# 06-AD9546_TimestampInputs.net
KiCad netlist of a schematic drawn in Altium Designer
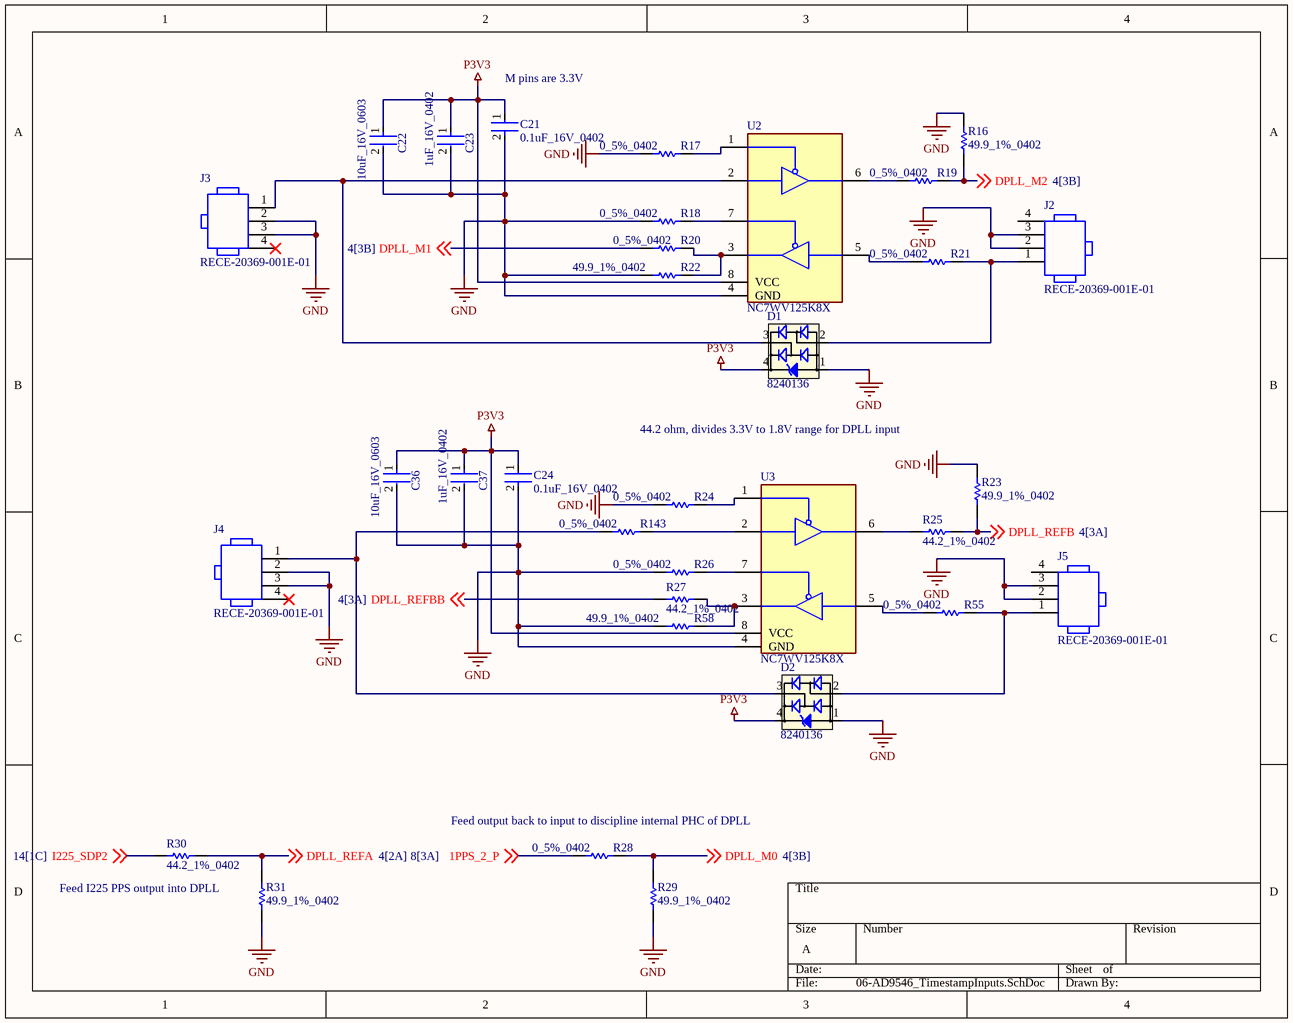
[diagram p0: 06-AD9546_TimestampInputs.SchDoc]

(export (version "E")
  (design (tool "Eeschema 10.0.6"))
  (components
    (comp (ref "C21")
      (value "GRM155R71C104KA88D")
      (footprint "FP-GRM15-MFG")
      (description "CAP CER 0.1UF 16V X7R 0402")
      (fields
        (field (name "TOLERANCE") "10%")
        (field (name "OCTOPART") "https://octopart.com/grm155r71c104ka88d-murata-196880")
        (field (name "DIGIKEY DESCRIPTION") "0.1uF_16V_0402")
      )
      (libsource (lib "Altium Content Vault") (part "236180d848d6139a670b325ea6854c9"))
    )
    (comp (ref "C22")
      (value "10uF_16V_0603")
      (footprint "FP-C1608-MFG")
      (description "CAP CER 10UF 16V X5R 0603")
      (fields
        (field (name "OCTOPART") "https://octopart.com/c1608x5r1c106m080ab-tdk-26013480")
        (field (name "MANUFACTURER") "TDK Corporation")
      )
      (libsource (lib "Altium Content Vault") (part "11868f565c42a9108669ba33697ecf6"))
    )
    (comp (ref "C23")
      (value "1uF_16V_0402")
      (footprint "FP-0402-L_1_0_0_05-W_0_5-IPC_C")
      (description "None")
      (fields (field (name "TOLERANCE") "20%") (field (name "VOLTAGE") "16V"))
      (libsource (lib "Altium Content Vault") (part "b4654b650e69147ec39a6b967a45e02"))
    )
    (comp (ref "C24")
      (value "GRM155R71C104KA88D")
      (footprint "FP-GRM15-MFG")
      (description "CAP CER 0.1UF 16V X7R 0402")
      (fields
        (field (name "TOLERANCE") "10%")
        (field (name "OCTOPART") "https://octopart.com/grm155r71c104ka88d-murata-196880")
        (field (name "DIGIKEY DESCRIPTION") "0.1uF_16V_0402")
      )
      (libsource (lib "Altium Content Vault") (part "236180d848d6139a670b325ea6854c9"))
    )
    (comp (ref "C36")
      (value "10uF_16V_0603")
      (footprint "FP-C1608-MFG")
      (description "CAP CER 10UF 16V X5R 0603")
      (fields
        (field (name "OCTOPART") "https://octopart.com/c1608x5r1c106m080ab-tdk-26013480")
        (field (name "MANUFACTURER") "TDK Corporation")
      )
      (libsource (lib "Altium Content Vault") (part "11868f565c42a9108669ba33697ecf6"))
    )
    (comp (ref "C37")
      (value "1uF_16V_0402")
      (footprint "FP-0402-L_1_0_0_05-W_0_5-IPC_C")
      (description "None")
      (fields (field (name "TOLERANCE") "20%") (field (name "VOLTAGE") "16V"))
      (libsource (lib "Altium Content Vault") (part "b4654b650e69147ec39a6b967a45e02"))
    )
    (comp (ref "D1")
      (value "8240136")
      (footprint "SOT143-4L")
      (description "TVS Diode WE-TVS-HS, VRWM=3.3V")
      (fields (field (name "MANUFACTURER") "Wuerth Elektronik"))
      (libsource (lib "Altium Content Vault") (part "WE-TVS-HS-4"))
    )
    (comp (ref "D2")
      (value "8240136")
      (footprint "SOT143-4L")
      (description "TVS Diode WE-TVS-HS, VRWM=3.3V")
      (fields (field (name "MANUFACTURER") "Wuerth Elektronik"))
      (libsource (lib "Altium Content Vault") (part "WE-TVS-HS-4"))
    )
    (comp (ref "J2")
      (value "RECE-20369-001E-01")
      (footprint "TG-RECE-20369-001E-4_V")
      (description "RF Connector, Onboard Receptacle, IPEX MHFIII")
      (fields (field (name "MANUFACTURER") "Taoglas"))
      (libsource (lib "Altium Content Vault") (part "TG-RECE-20369-001E-01-4"))
    )
    (comp (ref "J3")
      (value "RECE-20369-001E-01")
      (footprint "TG-RECE-20369-001E-4_V")
      (description "RF Connector, Onboard Receptacle, IPEX MHFIII")
      (fields (field (name "MANUFACTURER") "Taoglas"))
      (libsource (lib "Altium Content Vault") (part "TG-RECE-20369-001E-01-4"))
    )
    (comp (ref "J4")
      (value "RECE-20369-001E-01")
      (footprint "TG-RECE-20369-001E-4_V")
      (description "RF Connector, Onboard Receptacle, IPEX MHFIII")
      (fields (field (name "MANUFACTURER") "Taoglas"))
      (libsource (lib "Altium Content Vault") (part "TG-RECE-20369-001E-01-4"))
    )
    (comp (ref "J5")
      (value "RECE-20369-001E-01")
      (footprint "TG-RECE-20369-001E-4_V")
      (description "RF Connector, Onboard Receptacle, IPEX MHFIII")
      (fields (field (name "MANUFACTURER") "Taoglas"))
      (libsource (lib "Altium Content Vault") (part "TG-RECE-20369-001E-01-4"))
    )
    (comp (ref "R16")
      (value "49.9_1%_0402")
      (footprint "RESC1005X40X25NL05T05")
      (fields (field (name "MANUFACTURER") "Panasonic") (field (name "PART NUMBER") "ERJ-2RKF49R9X"))
      (libsource (lib "Altium Content Vault") (part "RES"))
    )
    (comp (ref "R17")
      (value "0_5%_0402")
      (footprint "RESC1005X40X25LL10T10")
      (fields (field (name "MANUFACTURER") "KOA Speer") (field (name "PART NUMBER") "RK73Z1ETTP"))
      (libsource (lib "Altium Content Vault") (part "RES"))
    )
    (comp (ref "R18")
      (value "0_5%_0402")
      (footprint "RESC1005X40X25LL10T10")
      (fields (field (name "MANUFACTURER") "KOA Speer") (field (name "PART NUMBER") "RK73Z1ETTP"))
      (libsource (lib "Altium Content Vault") (part "RES"))
    )
    (comp (ref "R19")
      (value "0_5%_0402")
      (footprint "RESC1005X40X25LL10T10")
      (fields (field (name "MANUFACTURER") "KOA Speer") (field (name "PART NUMBER") "RK73Z1ETTP"))
      (libsource (lib "Altium Content Vault") (part "RES"))
    )
    (comp (ref "R20")
      (value "0_5%_0402")
      (footprint "RESC1005X40X25LL10T10")
      (fields (field (name "MANUFACTURER") "KOA Speer") (field (name "PART NUMBER") "RK73Z1ETTP"))
      (libsource (lib "Altium Content Vault") (part "RES"))
    )
    (comp (ref "R21")
      (value "0_5%_0402")
      (footprint "RESC1005X40X25LL10T10")
      (fields (field (name "MANUFACTURER") "KOA Speer") (field (name "PART NUMBER") "RK73Z1ETTP"))
      (libsource (lib "Altium Content Vault") (part "RES"))
    )
    (comp (ref "R22")
      (value "49.9_1%_0402")
      (footprint "RESC1005X40X25NL05T05")
      (fields (field (name "MANUFACTURER") "Panasonic") (field (name "PART NUMBER") "ERJ-2RKF49R9X"))
      (libsource (lib "Altium Content Vault") (part "RES"))
    )
    (comp (ref "R23")
      (value "49.9_1%_0402")
      (footprint "RESC1005X40X25NL05T05")
      (fields (field (name "MANUFACTURER") "Panasonic") (field (name "PART NUMBER") "ERJ-2RKF49R9X"))
      (libsource (lib "Altium Content Vault") (part "RES"))
    )
    (comp (ref "R24")
      (value "0_5%_0402")
      (footprint "RESC1005X40X25LL10T10")
      (fields (field (name "MANUFACTURER") "KOA Speer") (field (name "PART NUMBER") "RK73Z1ETTP"))
      (libsource (lib "Altium Content Vault") (part "RES"))
    )
    (comp (ref "R25")
      (value "44.2_1%_0402")
      (footprint "RESC1005X40X25LL05T05")
      (fields (field (name "MANUFACTURER") "Vishay Dale") (field (name "PART NUMBER") "CRCW040244R2FKED"))
      (libsource (lib "Altium Content Vault") (part "RES"))
    )
    (comp (ref "R26")
      (value "0_5%_0402")
      (footprint "RESC1005X40X25LL10T10")
      (fields (field (name "MANUFACTURER") "KOA Speer") (field (name "PART NUMBER") "RK73Z1ETTP"))
      (libsource (lib "Altium Content Vault") (part "RES"))
    )
    (comp (ref "R27")
      (value "44.2_1%_0402")
      (footprint "RESC1005X40X25LL05T05")
      (fields (field (name "MANUFACTURER") "Vishay Dale") (field (name "PART NUMBER") "CRCW040244R2FKED"))
      (libsource (lib "Altium Content Vault") (part "RES"))
    )
    (comp (ref "R28")
      (value "0_5%_0402")
      (footprint "RESC1005X40X25LL10T10")
      (fields (field (name "MANUFACTURER") "KOA Speer") (field (name "PART NUMBER") "RK73Z1ETTP"))
      (libsource (lib "Altium Content Vault") (part "RES"))
    )
    (comp (ref "R29")
      (value "49.9_1%_0402")
      (footprint "RESC1005X40X25NL05T05")
      (fields (field (name "MANUFACTURER") "Panasonic") (field (name "PART NUMBER") "ERJ-2RKF49R9X"))
      (libsource (lib "Altium Content Vault") (part "RES"))
    )
    (comp (ref "R30")
      (value "44.2_1%_0402")
      (footprint "RESC1005X40X25LL05T05")
      (fields (field (name "MANUFACTURER") "Vishay Dale") (field (name "PART NUMBER") "CRCW040244R2FKED"))
      (libsource (lib "Altium Content Vault") (part "RES"))
    )
    (comp (ref "R31")
      (value "49.9_1%_0402")
      (footprint "RESC1005X40X25NL05T05")
      (fields (field (name "MANUFACTURER") "Panasonic") (field (name "PART NUMBER") "ERJ-2RKF49R9X"))
      (libsource (lib "Altium Content Vault") (part "RES"))
    )
    (comp (ref "R55")
      (value "0_5%_0402")
      (footprint "RESC1005X40X25LL10T10")
      (fields (field (name "MANUFACTURER") "KOA Speer") (field (name "PART NUMBER") "RK73Z1ETTP"))
      (libsource (lib "Altium Content Vault") (part "RES"))
    )
    (comp (ref "R58")
      (value "49.9_1%_0402")
      (footprint "RESC1005X40X25NL05T05")
      (fields (field (name "MANUFACTURER") "Panasonic") (field (name "PART NUMBER") "ERJ-2RKF49R9X"))
      (libsource (lib "Altium Content Vault") (part "RES"))
    )
    (comp (ref "R143")
      (value "0_5%_0402")
      (footprint "RESC1005X40X25LL10T10")
      (fields (field (name "MANUFACTURER") "KOA Speer") (field (name "PART NUMBER") "RK73Z1ETTP"))
      (libsource (lib "Altium Content Vault") (part "RES"))
    )
    (comp (ref "U2")
      (value "NC7WV125K8X")
      (footprint "NC7WV125")
      (description "Integrated Circuit")
      (fields (field (name "MOUSER PART NUMBER") "512-NC7WV125K8X"))
      (libsource (lib "SamacSys") (part "NC7WV125K8X"))
    )
    (comp (ref "U3")
      (value "NC7WV125K8X")
      (footprint "NC7WV125")
      (description "Integrated Circuit")
      (fields (field (name "MOUSER PART NUMBER") "512-NC7WV125K8X"))
      (libsource (lib "SamacSys") (part "NC7WV125K8X"))
    )
  )
  (nets
    (net (code "1") (name "1PPS_2_P") (class "Default")
      (node (ref "R28") (pin "1") (pinfunction "1_1") (pintype "passive"))
    )
    (net (code "2") (name "DPLL_M0") (class "Default")
      (node (ref "R28") (pin "2") (pinfunction "2_2") (pintype "passive"))
      (node (ref "R29") (pin "2") (pinfunction "2_2") (pintype "passive"))
    )
    (net (code "3") (name "DPLL_M1") (class "Default")
      (node (ref "R20") (pin "1") (pinfunction "1_1") (pintype "passive"))
    )
    (net (code "4") (name "DPLL_M2") (class "Default")
      (node (ref "R16") (pin "1") (pinfunction "1_1") (pintype "passive"))
      (node (ref "R19") (pin "2") (pinfunction "2_2") (pintype "passive"))
    )
    (net (code "5") (name "DPLL_REFA") (class "Default")
      (node (ref "R30") (pin "2") (pinfunction "2_2") (pintype "passive"))
      (node (ref "R31") (pin "2") (pinfunction "2_2") (pintype "passive"))
    )
    (net (code "6") (name "DPLL_REFB") (class "Default")
      (node (ref "R23") (pin "1") (pinfunction "1_1") (pintype "passive"))
      (node (ref "R25") (pin "2") (pinfunction "2_2") (pintype "passive"))
    )
    (net (code "7") (name "DPLL_REFBB") (class "Default")
      (node (ref "R27") (pin "1") (pinfunction "1_1") (pintype "passive"))
    )
    (net (code "8") (name "GND") (class "Default")
      (node (ref "C21") (pin "2") (pinfunction "2_2") (pintype "passive"))
      (node (ref "C22") (pin "2") (pinfunction "2_2") (pintype "passive"))
      (node (ref "C23") (pin "2") (pinfunction "2_2") (pintype "passive"))
      (node (ref "C24") (pin "2") (pinfunction "2_2") (pintype "passive"))
      (node (ref "C36") (pin "2") (pinfunction "2_2") (pintype "passive"))
      (node (ref "C37") (pin "2") (pinfunction "2_2") (pintype "passive"))
      (node (ref "D1") (pin "1") (pinfunction "GND_1") (pintype "passive"))
      (node (ref "D2") (pin "1") (pinfunction "GND_1") (pintype "passive"))
      (node (ref "J2") (pin "2") (pinfunction "2_2") (pintype "passive"))
      (node (ref "J2") (pin "3") (pinfunction "3_3") (pintype "passive"))
      (node (ref "J3") (pin "2") (pinfunction "2_2") (pintype "passive"))
      (node (ref "J3") (pin "3") (pinfunction "3_3") (pintype "passive"))
      (node (ref "J4") (pin "2") (pinfunction "2_2") (pintype "passive"))
      (node (ref "J4") (pin "3") (pinfunction "3_3") (pintype "passive"))
      (node (ref "J5") (pin "2") (pinfunction "2_2") (pintype "passive"))
      (node (ref "J5") (pin "3") (pinfunction "3_3") (pintype "passive"))
      (node (ref "R16") (pin "2") (pinfunction "2_2") (pintype "passive"))
      (node (ref "R17") (pin "1") (pinfunction "1_1") (pintype "passive"))
      (node (ref "R18") (pin "1") (pinfunction "1_1") (pintype "passive"))
      (node (ref "R22") (pin "2") (pinfunction "2_2") (pintype "passive"))
      (node (ref "R23") (pin "2") (pinfunction "2_2") (pintype "passive"))
      (node (ref "R24") (pin "1") (pinfunction "1_1") (pintype "passive"))
      (node (ref "R26") (pin "1") (pinfunction "1_1") (pintype "passive"))
      (node (ref "R29") (pin "1") (pinfunction "1_1") (pintype "passive"))
      (node (ref "R31") (pin "1") (pinfunction "1_1") (pintype "passive"))
      (node (ref "R58") (pin "2") (pinfunction "2_2") (pintype "passive"))
      (node (ref "U2") (pin "4") (pinfunction "GND_4") (pintype "passive"))
      (node (ref "U3") (pin "4") (pinfunction "GND_4") (pintype "passive"))
    )
    (net (code "9") (name "I225_SDP2") (class "Default")
      (node (ref "R30") (pin "1") (pinfunction "1_1") (pintype "passive"))
    )
    (net (code "10") (name "Net-(D1-I{slash}O1)") (class "Default")
      (node (ref "D1") (pin "2") (pinfunction "I/O1_2") (pintype "passive"))
      (node (ref "J2") (pin "1") (pinfunction "1_1") (pintype "passive"))
      (node (ref "R21") (pin "2") (pinfunction "2_2") (pintype "passive"))
    )
    (net (code "11") (name "Net-(D1-I{slash}O2)") (class "Default")
      (node (ref "D1") (pin "3") (pinfunction "I/O2_3") (pintype "passive"))
      (node (ref "J3") (pin "1") (pinfunction "1_1") (pintype "passive"))
      (node (ref "U2") (pin "2") (pintype "passive"))
    )
    (net (code "12") (name "Net-(D2-I{slash}O1)") (class "Default")
      (node (ref "D2") (pin "2") (pinfunction "I/O1_2") (pintype "passive"))
      (node (ref "J5") (pin "1") (pinfunction "1_1") (pintype "passive"))
      (node (ref "R55") (pin "2") (pinfunction "2_2") (pintype "passive"))
    )
    (net (code "13") (name "Net-(D2-I{slash}O2)") (class "Default")
      (node (ref "D2") (pin "3") (pinfunction "I/O2_3") (pintype "passive"))
      (node (ref "J4") (pin "1") (pinfunction "1_1") (pintype "passive"))
      (node (ref "R143") (pin "1") (pinfunction "1_1") (pintype "passive"))
    )
    (net (code "14") (name "Net-(R17-Pad2)") (class "Default")
      (node (ref "R17") (pin "2") (pinfunction "2_2") (pintype "passive"))
      (node (ref "U2") (pin "1") (pintype "passive"))
    )
    (net (code "15") (name "Net-(R18-Pad2)") (class "Default")
      (node (ref "R18") (pin "2") (pinfunction "2_2") (pintype "passive"))
      (node (ref "U2") (pin "7") (pintype "passive"))
    )
    (net (code "16") (name "Net-(R19-Pad1)") (class "Default")
      (node (ref "R19") (pin "1") (pinfunction "1_1") (pintype "passive"))
      (node (ref "U2") (pin "6") (pintype "passive"))
    )
    (net (code "17") (name "Net-(R20-Pad2)") (class "Default")
      (node (ref "R20") (pin "2") (pinfunction "2_2") (pintype "passive"))
      (node (ref "R22") (pin "1") (pinfunction "1_1") (pintype "passive"))
      (node (ref "U2") (pin "3") (pintype "passive"))
    )
    (net (code "18") (name "Net-(R21-Pad1)") (class "Default")
      (node (ref "R21") (pin "1") (pinfunction "1_1") (pintype "passive"))
      (node (ref "U2") (pin "5") (pintype "passive"))
    )
    (net (code "19") (name "Net-(R24-Pad2)") (class "Default")
      (node (ref "R24") (pin "2") (pinfunction "2_2") (pintype "passive"))
      (node (ref "U3") (pin "1") (pintype "passive"))
    )
    (net (code "20") (name "Net-(R25-Pad1)") (class "Default")
      (node (ref "R25") (pin "1") (pinfunction "1_1") (pintype "passive"))
      (node (ref "U3") (pin "6") (pintype "passive"))
    )
    (net (code "21") (name "Net-(R26-Pad2)") (class "Default")
      (node (ref "R26") (pin "2") (pinfunction "2_2") (pintype "passive"))
      (node (ref "U3") (pin "7") (pintype "passive"))
    )
    (net (code "22") (name "Net-(R27-Pad2)") (class "Default")
      (node (ref "R27") (pin "2") (pinfunction "2_2") (pintype "passive"))
      (node (ref "R58") (pin "1") (pinfunction "1_1") (pintype "passive"))
      (node (ref "U3") (pin "3") (pintype "passive"))
    )
    (net (code "23") (name "Net-(R55-Pad1)") (class "Default")
      (node (ref "R55") (pin "1") (pinfunction "1_1") (pintype "passive"))
      (node (ref "U3") (pin "5") (pintype "passive"))
    )
    (net (code "24") (name "Net-(R143-Pad2)") (class "Default")
      (node (ref "R143") (pin "2") (pinfunction "2_2") (pintype "passive"))
      (node (ref "U3") (pin "2") (pintype "passive"))
    )
    (net (code "25") (name "P3V3") (class "Default")
      (node (ref "C21") (pin "1") (pinfunction "1_1") (pintype "passive"))
      (node (ref "C22") (pin "1") (pinfunction "1_1") (pintype "passive"))
      (node (ref "C23") (pin "1") (pinfunction "1_1") (pintype "passive"))
      (node (ref "C24") (pin "1") (pinfunction "1_1") (pintype "passive"))
      (node (ref "C36") (pin "1") (pinfunction "1_1") (pintype "passive"))
      (node (ref "C37") (pin "1") (pinfunction "1_1") (pintype "passive"))
      (node (ref "D1") (pin "4") (pinfunction "VDD_4") (pintype "passive"))
      (node (ref "D2") (pin "4") (pinfunction "VDD_4") (pintype "passive"))
      (node (ref "U2") (pin "8") (pinfunction "VCC_8") (pintype "passive"))
      (node (ref "U3") (pin "8") (pinfunction "VCC_8") (pintype "passive"))
    )
    (net (code "26") (name "unconnected-(J2-Pad4)") (class "Default")
      (node (ref "J2") (pin "4") (pinfunction "4_4") (pintype "passive"))
    )
    (net (code "27") (name "unconnected-(J3-Pad4)") (class "Default")
      (node (ref "J3") (pin "4") (pinfunction "4_4") (pintype "passive+no_connect"))
    )
    (net (code "28") (name "unconnected-(J4-Pad4)") (class "Default")
      (node (ref "J4") (pin "4") (pinfunction "4_4") (pintype "passive+no_connect"))
    )
    (net (code "29") (name "unconnected-(J5-Pad4)") (class "Default")
      (node (ref "J5") (pin "4") (pinfunction "4_4") (pintype "passive"))
    )
  )
)
